# SCH_USB-Hub_2025-02-22.net
KiCad netlist of a schematic drawn in EasyEDA
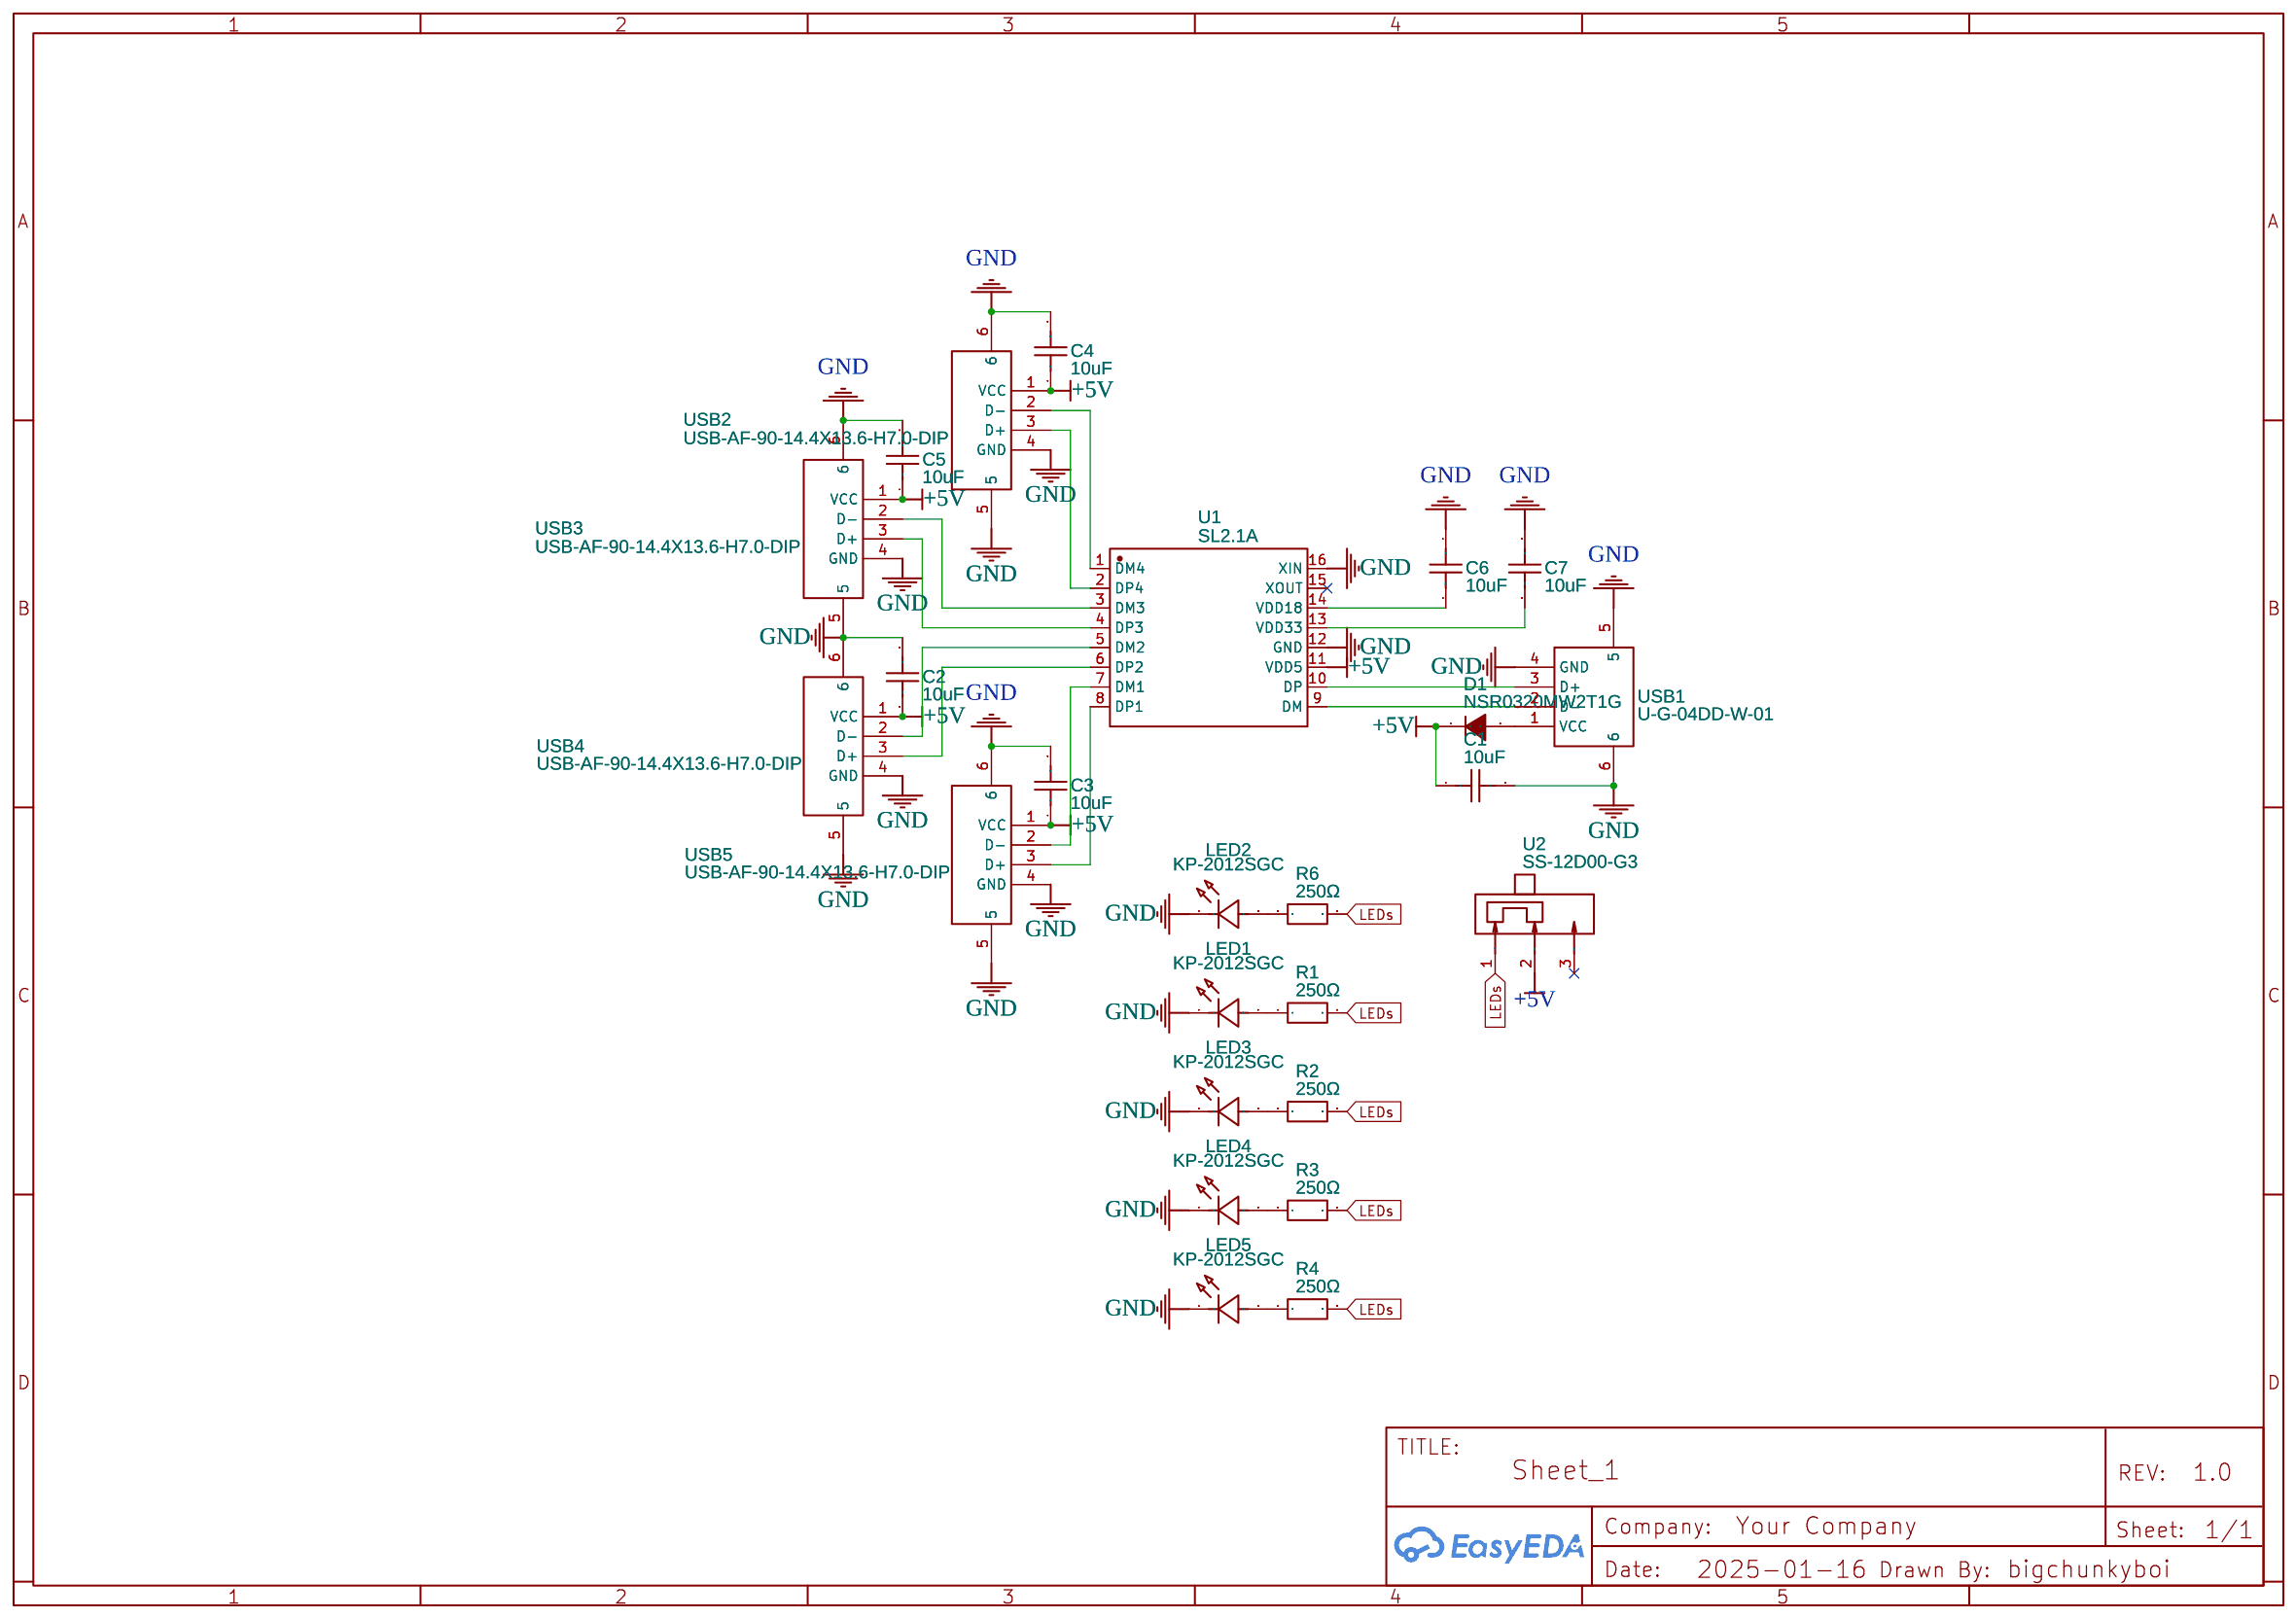
[diagram p0: schematic sheet]

(export (version "E")
  (design (tool "Eeschema 10.0.6"))
  (components
    (comp (ref "C1")
      (value "10uF")
      (fields
        (field (name "Manufacturer Part") "CL10A106KP8NNNC")
        (field (name "Manufacturer") "SAMSUNG(三星)")
      )
      (libsource (lib "") (part "CL10A106KP8NNNC_2"))
    )
    (comp (ref "C2")
      (value "10uF")
      (fields
        (field (name "Manufacturer Part") "CL10A106KP8NNNC")
        (field (name "Manufacturer") "SAMSUNG(三星)")
      )
      (libsource (lib "") (part "CL10A106KP8NNNC"))
    )
    (comp (ref "C3")
      (value "10uF")
      (fields
        (field (name "Manufacturer Part") "CL10A106KP8NNNC")
        (field (name "Manufacturer") "SAMSUNG(三星)")
      )
      (libsource (lib "") (part "CL10A106KP8NNNC"))
    )
    (comp (ref "C4")
      (value "10uF")
      (fields
        (field (name "Manufacturer Part") "CL10A106KP8NNNC")
        (field (name "Manufacturer") "SAMSUNG(三星)")
      )
      (libsource (lib "") (part "CL10A106KP8NNNC"))
    )
    (comp (ref "C5")
      (value "10uF")
      (fields
        (field (name "Manufacturer Part") "CL10A106KP8NNNC")
        (field (name "Manufacturer") "SAMSUNG(三星)")
      )
      (libsource (lib "") (part "CL10A106KP8NNNC"))
    )
    (comp (ref "C6")
      (value "10uF")
      (fields
        (field (name "Manufacturer Part") "CL10A106KP8NNNC")
        (field (name "Manufacturer") "SAMSUNG(三星)")
      )
      (libsource (lib "") (part "CL10A106KP8NNNC_1"))
    )
    (comp (ref "C7")
      (value "10uF")
      (fields
        (field (name "Manufacturer Part") "CL10A106KP8NNNC")
        (field (name "Manufacturer") "SAMSUNG(三星)")
      )
      (libsource (lib "") (part "CL10A106KP8NNNC_1"))
    )
    (comp (ref "D1")
      (value "NSR0320MW2T1G")
      (fields (field (name "Manufacturer") "onsemi(安森美)"))
      (libsource (lib "") (part "NSR0320MW2T1G"))
    )
    (comp (ref "LED1")
      (value "KP-2012SGC")
      (fields (field (name "Manufacturer") "Kingbright"))
      (libsource (lib "") (part "KP-2012SGC"))
    )
    (comp (ref "LED2")
      (value "KP-2012SGC")
      (fields (field (name "Manufacturer") "Kingbright"))
      (libsource (lib "") (part "KP-2012SGC"))
    )
    (comp (ref "LED3")
      (value "KP-2012SGC")
      (fields (field (name "Manufacturer") "Kingbright"))
      (libsource (lib "") (part "KP-2012SGC"))
    )
    (comp (ref "LED4")
      (value "KP-2012SGC")
      (fields (field (name "Manufacturer") "Kingbright"))
      (libsource (lib "") (part "KP-2012SGC"))
    )
    (comp (ref "LED5")
      (value "KP-2012SGC")
      (fields (field (name "Manufacturer") "Kingbright"))
      (libsource (lib "") (part "KP-2012SGC"))
    )
    (comp (ref "R1")
      (value "250Ω")
      (fields (field (name "Manufacturer Part") "ARG03DTC2500") (field (name "Manufacturer") "Viking(光颉)"))
      (libsource (lib "") (part "ARG03DTC2500"))
    )
    (comp (ref "R2")
      (value "250Ω")
      (fields (field (name "Manufacturer Part") "ARG03DTC2500") (field (name "Manufacturer") "Viking(光颉)"))
      (libsource (lib "") (part "ARG03DTC2500"))
    )
    (comp (ref "R3")
      (value "250Ω")
      (fields (field (name "Manufacturer Part") "ARG03DTC2500") (field (name "Manufacturer") "Viking(光颉)"))
      (libsource (lib "") (part "ARG03DTC2500"))
    )
    (comp (ref "R4")
      (value "250Ω")
      (fields (field (name "Manufacturer Part") "ARG03DTC2500") (field (name "Manufacturer") "Viking(光颉)"))
      (libsource (lib "") (part "ARG03DTC2500"))
    )
    (comp (ref "R6")
      (value "250Ω")
      (fields (field (name "Manufacturer Part") "ARG03DTC2500") (field (name "Manufacturer") "Viking(光颉)"))
      (libsource (lib "") (part "ARG03DTC2500"))
    )
    (comp (ref "U1")
      (value "SL2.1A")
      (fields (field (name "Manufacturer") "CoreChips(和芯润德)"))
      (libsource (lib "") (part "SL2.1A"))
    )
    (comp (ref "U2")
      (value "SS-12D00-G3")
      (fields (field (name "Manufacturer") "SOFNG(硕方)"))
      (libsource (lib "") (part "SS-12D00-G3"))
    )
    (comp (ref "USB1")
      (value "U-G-04DD-W-01")
      (fields (field (name "Manufacturer Part") "U-G-O4DD-W-1") (field (name "Manufacturer") "韩国韩荣"))
      (libsource (lib "") (part "U-G-04DD-W-01"))
    )
    (comp (ref "USB2")
      (value "USB-AF-90-14.4X13.6-H7.0-DIP")
      (fields (field (name "Manufacturer Part") "903-131A1011D10100") (field (name "Manufacturer") "精拓金"))
      (libsource (lib "") (part "USB-AF-90-14.4X13.6-H7.0-DIP"))
    )
    (comp (ref "USB3")
      (value "USB-AF-90-14.4X13.6-H7.0-DIP")
      (fields (field (name "Manufacturer Part") "903-131A1011D10100") (field (name "Manufacturer") "精拓金"))
      (libsource (lib "") (part "USB-AF-90-14.4X13.6-H7.0-DIP"))
    )
    (comp (ref "USB4")
      (value "USB-AF-90-14.4X13.6-H7.0-DIP")
      (fields (field (name "Manufacturer Part") "903-131A1011D10100") (field (name "Manufacturer") "精拓金"))
      (libsource (lib "") (part "USB-AF-90-14.4X13.6-H7.0-DIP"))
    )
    (comp (ref "USB5")
      (value "USB-AF-90-14.4X13.6-H7.0-DIP")
      (fields (field (name "Manufacturer Part") "903-131A1011D10100") (field (name "Manufacturer") "精拓金"))
      (libsource (lib "") (part "USB-AF-90-14.4X13.6-H7.0-DIP"))
    )
  )
  (nets
    (net (code "1") (name "+5V") (class "Default")
      (node (ref "C1") (pin "1") (pinfunction "1_1") (pintype "unspecified"))
      (node (ref "C2") (pin "1") (pinfunction "1_1") (pintype "unspecified"))
      (node (ref "C3") (pin "1") (pinfunction "1_1") (pintype "unspecified"))
      (node (ref "C4") (pin "1") (pinfunction "1_1") (pintype "unspecified"))
      (node (ref "C5") (pin "1") (pinfunction "1_1") (pintype "unspecified"))
      (node (ref "D1") (pin "1") (pinfunction "C_1") (pintype "unspecified"))
      (node (ref "U1") (pin "11") (pinfunction "VDD5_11") (pintype "unspecified"))
      (node (ref "U2") (pin "2") (pinfunction "2_2") (pintype "unspecified"))
      (node (ref "USB2") (pin "1") (pinfunction "VCC_1") (pintype "unspecified"))
      (node (ref "USB3") (pin "1") (pinfunction "VCC_1") (pintype "unspecified"))
      (node (ref "USB4") (pin "1") (pinfunction "VCC_1") (pintype "unspecified"))
      (node (ref "USB5") (pin "1") (pinfunction "VCC_1") (pintype "unspecified"))
    )
    (net (code "2") (name "GND") (class "Default")
      (node (ref "C1") (pin "2") (pinfunction "2_2") (pintype "unspecified"))
      (node (ref "C2") (pin "2") (pinfunction "2_2") (pintype "unspecified"))
      (node (ref "C3") (pin "2") (pinfunction "2_2") (pintype "unspecified"))
      (node (ref "C4") (pin "2") (pinfunction "2_2") (pintype "unspecified"))
      (node (ref "C5") (pin "2") (pinfunction "2_2") (pintype "unspecified"))
      (node (ref "C6") (pin "1") (pinfunction "1_1") (pintype "unspecified"))
      (node (ref "C7") (pin "1") (pinfunction "1_1") (pintype "unspecified"))
      (node (ref "LED1") (pin "1") (pinfunction "K_1") (pintype "unspecified"))
      (node (ref "LED2") (pin "1") (pinfunction "K_1") (pintype "unspecified"))
      (node (ref "LED3") (pin "1") (pinfunction "K_1") (pintype "unspecified"))
      (node (ref "LED4") (pin "1") (pinfunction "K_1") (pintype "unspecified"))
      (node (ref "LED5") (pin "1") (pinfunction "K_1") (pintype "unspecified"))
      (node (ref "U1") (pin "12") (pinfunction "GND_12") (pintype "unspecified"))
      (node (ref "U1") (pin "16") (pinfunction "XIN_16") (pintype "unspecified"))
      (node (ref "USB1") (pin "4") (pinfunction "GND_4") (pintype "unspecified"))
      (node (ref "USB1") (pin "5") (pinfunction "5_5") (pintype "unspecified"))
      (node (ref "USB1") (pin "6") (pinfunction "6_6") (pintype "unspecified"))
      (node (ref "USB2") (pin "4") (pinfunction "GND_4") (pintype "unspecified"))
      (node (ref "USB2") (pin "5") (pinfunction "5_5") (pintype "unspecified"))
      (node (ref "USB2") (pin "6") (pinfunction "6_6") (pintype "unspecified"))
      (node (ref "USB3") (pin "4") (pinfunction "GND_4") (pintype "unspecified"))
      (node (ref "USB3") (pin "5") (pinfunction "5_5") (pintype "unspecified"))
      (node (ref "USB3") (pin "6") (pinfunction "6_6") (pintype "unspecified"))
      (node (ref "USB4") (pin "4") (pinfunction "GND_4") (pintype "unspecified"))
      (node (ref "USB4") (pin "5") (pinfunction "5_5") (pintype "unspecified"))
      (node (ref "USB4") (pin "6") (pinfunction "6_6") (pintype "unspecified"))
      (node (ref "USB5") (pin "4") (pinfunction "GND_4") (pintype "unspecified"))
      (node (ref "USB5") (pin "5") (pinfunction "5_5") (pintype "unspecified"))
      (node (ref "USB5") (pin "6") (pinfunction "6_6") (pintype "unspecified"))
    )
    (net (code "3") (name "LEDs") (class "Default")
      (node (ref "R1") (pin "2") (pinfunction "2_2") (pintype "unspecified"))
      (node (ref "R2") (pin "2") (pinfunction "2_2") (pintype "unspecified"))
      (node (ref "R3") (pin "2") (pinfunction "2_2") (pintype "unspecified"))
      (node (ref "R4") (pin "2") (pinfunction "2_2") (pintype "unspecified"))
      (node (ref "R6") (pin "2") (pinfunction "2_2") (pintype "unspecified"))
      (node (ref "U2") (pin "1") (pinfunction "1_1") (pintype "unspecified"))
    )
    (net (code "4") (name "Net-(D1-A)") (class "Default")
      (node (ref "D1") (pin "2") (pinfunction "A_2") (pintype "unspecified"))
      (node (ref "USB1") (pin "1") (pinfunction "VCC_1") (pintype "unspecified"))
    )
    (net (code "5") (name "Net-(LED1-A)") (class "Default")
      (node (ref "LED1") (pin "2") (pinfunction "A_2") (pintype "unspecified"))
      (node (ref "R1") (pin "1") (pinfunction "1_1") (pintype "unspecified"))
    )
    (net (code "6") (name "Net-(LED2-A)") (class "Default")
      (node (ref "LED2") (pin "2") (pinfunction "A_2") (pintype "unspecified"))
      (node (ref "R6") (pin "1") (pinfunction "1_1") (pintype "unspecified"))
    )
    (net (code "7") (name "Net-(LED3-A)") (class "Default")
      (node (ref "LED3") (pin "2") (pinfunction "A_2") (pintype "unspecified"))
      (node (ref "R2") (pin "1") (pinfunction "1_1") (pintype "unspecified"))
    )
    (net (code "8") (name "Net-(LED4-A)") (class "Default")
      (node (ref "LED4") (pin "2") (pinfunction "A_2") (pintype "unspecified"))
      (node (ref "R3") (pin "1") (pinfunction "1_1") (pintype "unspecified"))
    )
    (net (code "9") (name "Net-(LED5-A)") (class "Default")
      (node (ref "LED5") (pin "2") (pinfunction "A_2") (pintype "unspecified"))
      (node (ref "R4") (pin "1") (pinfunction "1_1") (pintype "unspecified"))
    )
    (net (code "10") (name "Net-(U1-DM)") (class "Default")
      (node (ref "U1") (pin "9") (pinfunction "DM_9") (pintype "unspecified"))
      (node (ref "USB1") (pin "2") (pinfunction "D-_2") (pintype "unspecified"))
    )
    (net (code "11") (name "Net-(U1-DM1)") (class "Default")
      (node (ref "U1") (pin "7") (pinfunction "DM1_7") (pintype "unspecified"))
      (node (ref "USB5") (pin "2") (pinfunction "D-_2") (pintype "unspecified"))
    )
    (net (code "12") (name "Net-(U1-DM2)") (class "Default")
      (node (ref "U1") (pin "5") (pinfunction "DM2_5") (pintype "unspecified"))
      (node (ref "USB4") (pin "2") (pinfunction "D-_2") (pintype "unspecified"))
    )
    (net (code "13") (name "Net-(U1-DM3)") (class "Default")
      (node (ref "U1") (pin "3") (pinfunction "DM3_3") (pintype "unspecified"))
      (node (ref "USB3") (pin "2") (pinfunction "D-_2") (pintype "unspecified"))
    )
    (net (code "14") (name "Net-(U1-DM4)") (class "Default")
      (node (ref "U1") (pin "1") (pinfunction "DM4_1") (pintype "unspecified"))
      (node (ref "USB2") (pin "2") (pinfunction "D-_2") (pintype "unspecified"))
    )
    (net (code "15") (name "Net-(U1-DP)") (class "Default")
      (node (ref "U1") (pin "10") (pinfunction "DP_10") (pintype "unspecified"))
      (node (ref "USB1") (pin "3") (pinfunction "D+_3") (pintype "unspecified"))
    )
    (net (code "16") (name "Net-(U1-DP1)") (class "Default")
      (node (ref "U1") (pin "8") (pinfunction "DP1_8") (pintype "unspecified"))
      (node (ref "USB5") (pin "3") (pinfunction "D+_3") (pintype "unspecified"))
    )
    (net (code "17") (name "Net-(U1-DP2)") (class "Default")
      (node (ref "U1") (pin "6") (pinfunction "DP2_6") (pintype "unspecified"))
      (node (ref "USB4") (pin "3") (pinfunction "D+_3") (pintype "unspecified"))
    )
    (net (code "18") (name "Net-(U1-DP3)") (class "Default")
      (node (ref "U1") (pin "4") (pinfunction "DP3_4") (pintype "unspecified"))
      (node (ref "USB3") (pin "3") (pinfunction "D+_3") (pintype "unspecified"))
    )
    (net (code "19") (name "Net-(U1-DP4)") (class "Default")
      (node (ref "U1") (pin "2") (pinfunction "DP4_2") (pintype "unspecified"))
      (node (ref "USB2") (pin "3") (pinfunction "D+_3") (pintype "unspecified"))
    )
    (net (code "20") (name "Net-(U1-VDD18)") (class "Default")
      (node (ref "C6") (pin "2") (pinfunction "2_2") (pintype "unspecified"))
      (node (ref "U1") (pin "14") (pinfunction "VDD18_14") (pintype "unspecified"))
    )
    (net (code "21") (name "Net-(U1-VDD33)") (class "Default")
      (node (ref "C7") (pin "2") (pinfunction "2_2") (pintype "unspecified"))
      (node (ref "U1") (pin "13") (pinfunction "VDD33_13") (pintype "unspecified"))
    )
    (net (code "22") (name "unconnected-(U1-XOUT-Pad15)") (class "Default")
      (node (ref "U1") (pin "15") (pinfunction "XOUT_15") (pintype "unspecified+no_connect"))
    )
    (net (code "23") (name "unconnected-(U2-Pad3)") (class "Default")
      (node (ref "U2") (pin "3") (pinfunction "3_3") (pintype "unspecified+no_connect"))
    )
  )
)
